# STM32.net
KiCad netlist of a schematic drawn in Altium Designer
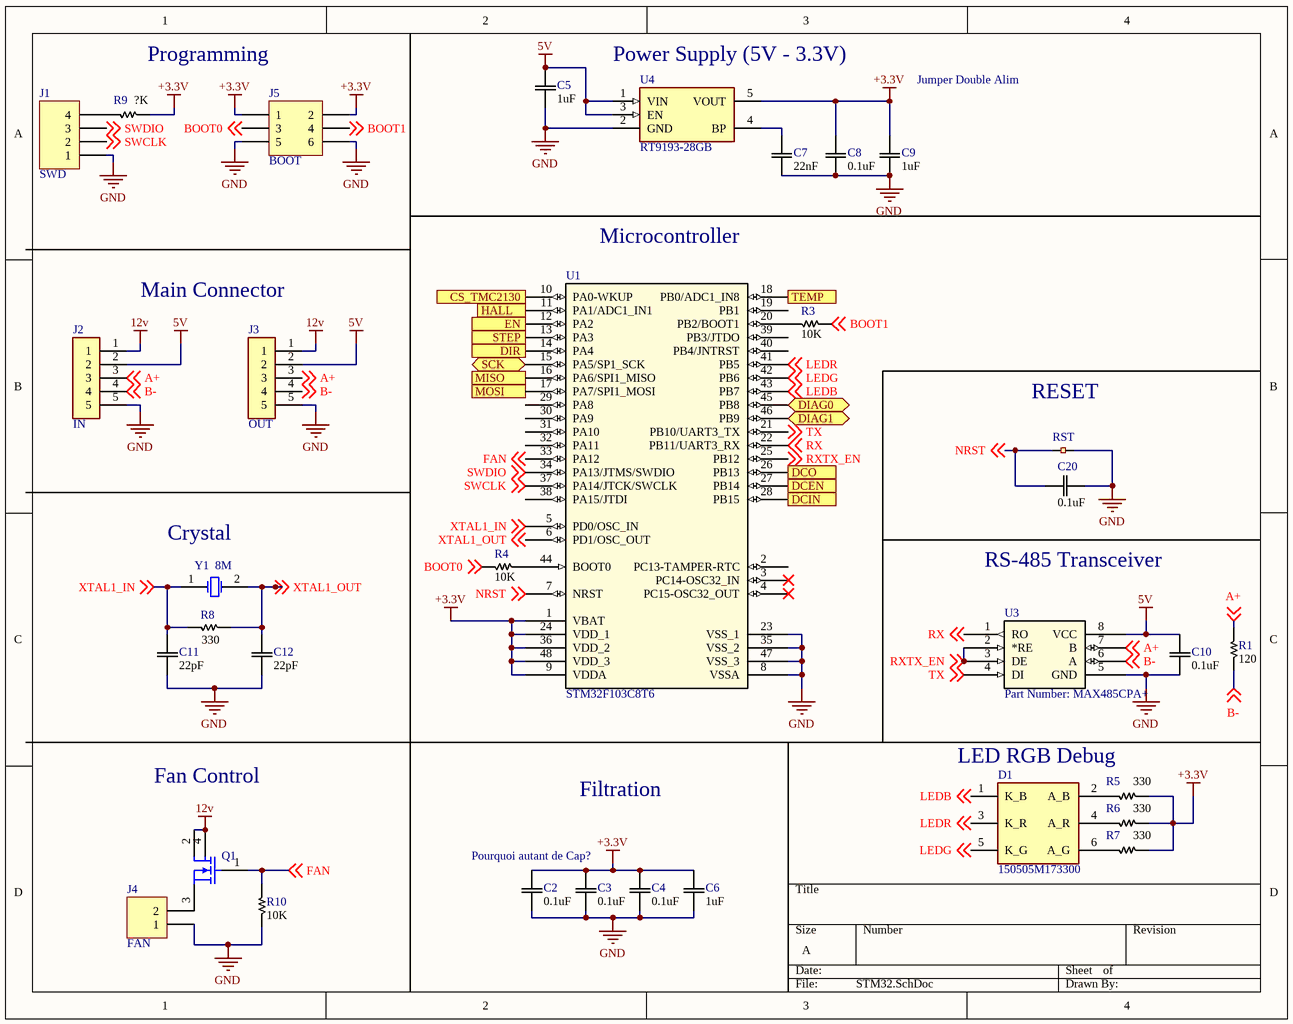
[diagram p0: STM32.SchDoc]

(export (version "E")
  (design (tool "Eeschema 10.0.6"))
  (components
    (comp (ref "C2")
      (value "0.1uF")
      (footprint "0603")
      (description "Capacitor SMD 1206")
      (fields
        (field (name "MANUFACTURER_PART_NUMBER") "12065A820JAT2A")
        (field (name "Comment") "Capacitor 1206")
        (field (name "COPYRIGHT") "Copyright (C) 2018 Accelerated Designs. All rights reserved")
      )
      (libsource (lib "Schematic_Emile") (part "Capacitor 1206"))
    )
    (comp (ref "C3")
      (value "0.1uF")
      (footprint "0603")
      (description "Capacitor SMD 1206")
      (fields
        (field (name "MANUFACTURER_PART_NUMBER") "12065A820JAT2A")
        (field (name "Comment") "Capacitor 1206")
        (field (name "COPYRIGHT") "Copyright (C) 2018 Accelerated Designs. All rights reserved")
      )
      (libsource (lib "Schematic_Emile") (part "Capacitor 1206"))
    )
    (comp (ref "C4")
      (value "0.1uF")
      (footprint "0603")
      (description "Capacitor SMD 1206")
      (fields
        (field (name "MANUFACTURER_PART_NUMBER") "12065A820JAT2A")
        (field (name "Comment") "Capacitor 1206")
        (field (name "COPYRIGHT") "Copyright (C) 2018 Accelerated Designs. All rights reserved")
      )
      (libsource (lib "Schematic_Emile") (part "Capacitor 1206"))
    )
    (comp (ref "C5")
      (value "1uF")
      (footprint "0603")
      (description "Capacitor SMD 1206")
      (fields
        (field (name "MANUFACTURER_PART_NUMBER") "12065A820JAT2A")
        (field (name "Comment") "Capacitor 1206")
        (field (name "COPYRIGHT") "Copyright (C) 2018 Accelerated Designs. All rights reserved")
      )
      (libsource (lib "Schematic_Emile") (part "Capacitor 1206"))
    )
    (comp (ref "C6")
      (value "1uF")
      (footprint "0603")
      (description "Capacitor SMD 1206")
      (fields
        (field (name "MANUFACTURER_PART_NUMBER") "12065A820JAT2A")
        (field (name "Comment") "Capacitor 1206")
        (field (name "COPYRIGHT") "Copyright (C) 2018 Accelerated Designs. All rights reserved")
      )
      (libsource (lib "Schematic_Emile") (part "Capacitor 1206"))
    )
    (comp (ref "C7")
      (value "22nF")
      (footprint "0603")
      (description "Capacitor SMD 1206")
      (fields
        (field (name "MANUFACTURER_PART_NUMBER") "12065A820JAT2A")
        (field (name "Comment") "Capacitor 1206")
        (field (name "COPYRIGHT") "Copyright (C) 2018 Accelerated Designs. All rights reserved")
      )
      (libsource (lib "Schematic_Emile") (part "Capacitor 1206"))
    )
    (comp (ref "C8")
      (value "0.1uF")
      (footprint "0603")
      (description "Capacitor SMD 1206")
      (fields
        (field (name "MANUFACTURER_PART_NUMBER") "12065A820JAT2A")
        (field (name "Comment") "Capacitor 1206")
        (field (name "COPYRIGHT") "Copyright (C) 2018 Accelerated Designs. All rights reserved")
      )
      (libsource (lib "Schematic_Emile") (part "Capacitor 1206"))
    )
    (comp (ref "C9")
      (value "1uF")
      (footprint "0603")
      (description "Capacitor SMD 1206")
      (fields
        (field (name "MANUFACTURER_PART_NUMBER") "12065A820JAT2A")
        (field (name "Comment") "Capacitor 1206")
        (field (name "COPYRIGHT") "Copyright (C) 2018 Accelerated Designs. All rights reserved")
      )
      (libsource (lib "Schematic_Emile") (part "Capacitor 1206"))
    )
    (comp (ref "C10")
      (value "0.1uF")
      (footprint "0603")
      (description "Capacitor SMD 1206")
      (fields
        (field (name "MANUFACTURER_PART_NUMBER") "12065A820JAT2A")
        (field (name "Comment") "Capacitor 1206")
        (field (name "COPYRIGHT") "Copyright (C) 2018 Accelerated Designs. All rights reserved")
      )
      (libsource (lib "Schematic_Emile") (part "Capacitor 1206"))
    )
    (comp (ref "C11")
      (value "22pF")
      (footprint "0603")
      (description "Capacitor SMD 1206")
      (fields
        (field (name "MANUFACTURER_PART_NUMBER") "12065A820JAT2A")
        (field (name "Comment") "Capacitor 1206")
        (field (name "COPYRIGHT") "Copyright (C) 2018 Accelerated Designs. All rights reserved")
      )
      (libsource (lib "Schematic_Emile") (part "Capacitor 1206"))
    )
    (comp (ref "C12")
      (value "22pF")
      (footprint "0603")
      (description "Capacitor SMD 1206")
      (fields
        (field (name "MANUFACTURER_PART_NUMBER") "12065A820JAT2A")
        (field (name "Comment") "Capacitor 1206")
        (field (name "COPYRIGHT") "Copyright (C) 2018 Accelerated Designs. All rights reserved")
      )
      (libsource (lib "Schematic_Emile") (part "Capacitor 1206"))
    )
    (comp (ref "C20")
      (value "0.1uF")
      (footprint "0603")
      (description "Capacitor SMD 1206")
      (fields
        (field (name "MANUFACTURER_PART_NUMBER") "12065A820JAT2A")
        (field (name "Comment") "Capacitor 1206")
        (field (name "COPYRIGHT") "Copyright (C) 2018 Accelerated Designs. All rights reserved")
      )
      (libsource (lib "Schematic_Emile") (part "Capacitor 1206"))
    )
    (comp (ref "D1")
      (value "150505M173300")
      (footprint "LED 5050")
      (description "LED")
      (fields
        (field (name "MOUSER PART NUMBER") "710-150505M173300")
        (field (name "RS PART NUMBER") "1766248P")
      )
      (libsource (lib "Schematic_Emile") (part "150505M173300"))
    )
    (comp (ref "J1")
      (value "SWD")
      (footprint "HDR1X4")
      (description "Header, 4-Pin")
      (fields (field (name "PUBLISHER") "Altium Limited"))
      (libsource (lib "Miscellaneous Connectors") (part "Header 4"))
    )
    (comp (ref "J2")
      (value "IN")
      (footprint "JST 5POS 2.5mm 90°")
      (description "Connector")
      (fields (field (name "MANUFACTURER_PART_NUMBER") "S5B-XH-A-1(LF)(SN)"))
      (libsource (lib "Schematic_Emile") (part "JST 5POS"))
    )
    (comp (ref "J3")
      (value "OUT")
      (footprint "JST 5POS 2.5mm 90°")
      (description "Connector")
      (fields (field (name "MANUFACTURER_PART_NUMBER") "S5B-XH-A-1(LF)(SN)"))
      (libsource (lib "Schematic_Emile") (part "JST 5POS"))
    )
    (comp (ref "J4")
      (value "FAN")
      (footprint "HDR1X2")
      (description "Header, 2-Pin")
      (fields (field (name "PUBLISHER") "Altium Limited"))
      (libsource (lib "Miscellaneous Connectors") (part "Header 2"))
    )
    (comp (ref "J5")
      (value "BOOT")
      (footprint "HDR2X3")
      (description "Header, 3-Pin, Dual row")
      (fields (field (name "PUBLISHER") "Altium Limited"))
      (libsource (lib "Miscellaneous Connectors") (part "Header 3X2"))
    )
    (comp (ref "Q1")
      (value "MOSFET N-CH")
      (footprint "SOT223_M")
      (description "55V 7A SOT223")
      (libsource (lib "Schematic_Emile") (part "MOSFET N-CH"))
    )
    (comp (ref "R1")
      (value "120")
      (footprint "0603")
      (description "Resistor 1206 SMD")
      (fields
        (field (name "MANUFACTURER_PART_NUMBER") "ERJ8CWFR024V")
        (field (name "Comment") "Resistor 1206")
        (field (name "COPYRIGHT") "Copyright (C) 2018 Accelerated Designs. All rights reserved")
      )
      (libsource (lib "Schematic_Emile") (part "Resistor 1206"))
    )
    (comp (ref "R3")
      (value "10K")
      (footprint "0603")
      (description "Resistor 1206 SMD")
      (fields
        (field (name "MANUFACTURER_PART_NUMBER") "ERJ8CWFR024V")
        (field (name "Comment") "Resistor 1206")
        (field (name "COPYRIGHT") "Copyright (C) 2018 Accelerated Designs. All rights reserved")
      )
      (libsource (lib "Schematic_Emile") (part "Resistor 1206"))
    )
    (comp (ref "R4")
      (value "10K")
      (footprint "0603")
      (description "Resistor 1206 SMD")
      (fields
        (field (name "MANUFACTURER_PART_NUMBER") "ERJ8CWFR024V")
        (field (name "Comment") "Resistor 1206")
        (field (name "COPYRIGHT") "Copyright (C) 2018 Accelerated Designs. All rights reserved")
      )
      (libsource (lib "Schematic_Emile") (part "Resistor 1206"))
    )
    (comp (ref "R5")
      (value "330")
      (footprint "0603")
      (description "Resistor 1206 SMD")
      (fields
        (field (name "MANUFACTURER_PART_NUMBER") "ERJ8CWFR024V")
        (field (name "Comment") "Resistor 1206")
        (field (name "COPYRIGHT") "Copyright (C) 2018 Accelerated Designs. All rights reserved")
      )
      (libsource (lib "Schematic_Emile") (part "Resistor 1206"))
    )
    (comp (ref "R6")
      (value "330")
      (footprint "0603")
      (description "Resistor 1206 SMD")
      (fields
        (field (name "MANUFACTURER_PART_NUMBER") "ERJ8CWFR024V")
        (field (name "Comment") "Resistor 1206")
        (field (name "COPYRIGHT") "Copyright (C) 2018 Accelerated Designs. All rights reserved")
      )
      (libsource (lib "Schematic_Emile") (part "Resistor 1206"))
    )
    (comp (ref "R7")
      (value "330")
      (footprint "0603")
      (description "Resistor 1206 SMD")
      (fields
        (field (name "MANUFACTURER_PART_NUMBER") "ERJ8CWFR024V")
        (field (name "Comment") "Resistor 1206")
        (field (name "COPYRIGHT") "Copyright (C) 2018 Accelerated Designs. All rights reserved")
      )
      (libsource (lib "Schematic_Emile") (part "Resistor 1206"))
    )
    (comp (ref "R8")
      (value "330")
      (footprint "0603")
      (description "Resistor 1206 SMD")
      (fields
        (field (name "MANUFACTURER_PART_NUMBER") "ERJ8CWFR024V")
        (field (name "Comment") "Resistor 1206")
        (field (name "COPYRIGHT") "Copyright (C) 2018 Accelerated Designs. All rights reserved")
      )
      (libsource (lib "Schematic_Emile") (part "Resistor 1206"))
    )
    (comp (ref "R9")
      (value "?K")
      (footprint "0603")
      (description "Resistor 1206 SMD")
      (fields
        (field (name "MANUFACTURER_PART_NUMBER") "ERJ8CWFR024V")
        (field (name "Comment") "Resistor 1206")
        (field (name "COPYRIGHT") "Copyright (C) 2018 Accelerated Designs. All rights reserved")
      )
      (libsource (lib "Schematic_Emile") (part "Resistor 1206"))
    )
    (comp (ref "R10")
      (value "10K")
      (footprint "0603")
      (description "Resistor 1206 SMD")
      (fields
        (field (name "MANUFACTURER_PART_NUMBER") "ERJ8CWFR024V")
        (field (name "Comment") "Resistor 1206")
        (field (name "COPYRIGHT") "Copyright (C) 2018 Accelerated Designs. All rights reserved")
      )
      (libsource (lib "Schematic_Emile") (part "Resistor 1206"))
    )
    (comp (ref "RST")
      (value "PAD")
      (footprint "PAD")
      (description "SMD Pad for contact")
      (libsource (lib "Schematic_Emile") (part "PAD"))
    )
    (comp (ref "U1")
      (value "STM32F103C8T6")
      (footprint "LQFP-48")
      (description "Integrated Circuit STM32")
      (fields (field (name "COPYRIGHT") "Copyright (C) 2018 Accelerated Designs. All rights reserved"))
      (libsource (lib "Schematic_Emile") (part "STM32F103C8T6"))
    )
    (comp (ref "U3")
      (value "Part Number: MAX485CPA+")
      (footprint "DIP 8 - 3D")
      (description "RS485 Communication")
      (fields
        (field (name "MANUFACTURER_PART_NUMBER") "MAX485CPA+")
        (field (name "COPYRIGHT") "Copyright (C) 2018 Accelerated Designs. All rights reserved")
      )
      (libsource (lib "Schematic_Emile") (part "MAX485CPA+"))
    )
    (comp (ref "U4")
      (value "RT9193-28GB")
      (footprint "SamacSys:SOT94P279X130-5N")
      (description "Voltage Regulator 3.3V")
      (libsource (lib "Schematic_Emile") (part "RT9193-28GB"))
    )
    (comp (ref "Y1")
      (value "8M")
      (footprint "ATS080B-E")
      (description "Crystal Oscillator")
      (fields (field (name "PUBLISHER") "Altium Limited"))
      (libsource (lib "Miscellaneous Devices") (part "XTAL"))
    )
  )
  (nets
    (net (code "1") (name "+3.3V") (class "Default")
      (node (ref "C2") (pin "2") (pinfunction "2_2") (pintype "passive"))
      (node (ref "C3") (pin "2") (pinfunction "2_2") (pintype "passive"))
      (node (ref "C4") (pin "2") (pinfunction "2_2") (pintype "passive"))
      (node (ref "C6") (pin "2") (pinfunction "2_2") (pintype "passive"))
      (node (ref "C8") (pin "2") (pinfunction "2_2") (pintype "passive"))
      (node (ref "C9") (pin "2") (pinfunction "2_2") (pintype "passive"))
      (node (ref "J5") (pin "1") (pinfunction "1_1") (pintype "passive"))
      (node (ref "J5") (pin "2") (pinfunction "2_2") (pintype "passive"))
      (node (ref "R5") (pin "2") (pinfunction "2_2") (pintype "passive"))
      (node (ref "R6") (pin "2") (pinfunction "2_2") (pintype "passive"))
      (node (ref "R7") (pin "2") (pinfunction "2_2") (pintype "passive"))
      (node (ref "R9") (pin "2") (pinfunction "2_2") (pintype "passive"))
      (node (ref "U1") (pin "1") (pinfunction "VBAT_1") (pintype "power_in"))
      (node (ref "U1") (pin "24") (pinfunction "VDD_1_24") (pintype "power_in"))
      (node (ref "U1") (pin "36") (pinfunction "VDD_2_36") (pintype "power_in"))
      (node (ref "U1") (pin "48") (pinfunction "VDD_3_48") (pintype "power_in"))
      (node (ref "U1") (pin "9") (pinfunction "VDDA_9") (pintype "power_in"))
      (node (ref "U4") (pin "5") (pinfunction "VOUT_5") (pintype "passive"))
    )
    (net (code "2") (name "/CS_TMC2130") (class "Default")
      (node (ref "U1") (pin "10") (pinfunction "PA0-WKUP_10") (pintype "bidirectional"))
    )
    (net (code "3") (name "/DCEN") (class "Default")
      (node (ref "U1") (pin "27") (pinfunction "PB14_27") (pintype "bidirectional"))
    )
    (net (code "4") (name "/DCIN") (class "Default")
      (node (ref "U1") (pin "28") (pinfunction "PB15_28") (pintype "bidirectional"))
    )
    (net (code "5") (name "/DCO") (class "Default")
      (node (ref "U1") (pin "26") (pinfunction "PB13_26") (pintype "bidirectional"))
    )
    (net (code "6") (name "/DIAG0") (class "Default")
      (node (ref "U1") (pin "45") (pinfunction "PB8_45") (pintype "bidirectional"))
    )
    (net (code "7") (name "/DIAG1") (class "Default")
      (node (ref "U1") (pin "46") (pinfunction "PB9_46") (pintype "bidirectional"))
    )
    (net (code "8") (name "/DIR") (class "Default")
      (node (ref "U1") (pin "14") (pinfunction "PA4_14") (pintype "bidirectional"))
    )
    (net (code "9") (name "/EN") (class "Default")
      (node (ref "U1") (pin "12") (pinfunction "PA2_12") (pintype "bidirectional"))
    )
    (net (code "10") (name "/HALL") (class "Default")
      (node (ref "U1") (pin "11") (pinfunction "PA1/ADC1_IN1_11") (pintype "bidirectional"))
    )
    (net (code "11") (name "/MISO") (class "Default")
      (node (ref "U1") (pin "16") (pinfunction "PA6/SPI1_MISO_16") (pintype "bidirectional"))
    )
    (net (code "12") (name "/MOSI") (class "Default")
      (node (ref "U1") (pin "17") (pinfunction "PA7/SPI1_MOSI_17") (pintype "bidirectional"))
    )
    (net (code "13") (name "/SCK") (class "Default")
      (node (ref "U1") (pin "15") (pinfunction "PA5/SP1_SCK_15") (pintype "bidirectional"))
    )
    (net (code "14") (name "/STEP") (class "Default")
      (node (ref "U1") (pin "13") (pinfunction "PA3_13") (pintype "bidirectional"))
    )
    (net (code "15") (name "/TEMP") (class "Default")
      (node (ref "U1") (pin "18") (pinfunction "PB0/ADC1_IN8_18") (pintype "bidirectional"))
    )
    (net (code "16") (name "5V") (class "Default")
      (node (ref "C10") (pin "2") (pinfunction "2_2") (pintype "passive"))
      (node (ref "C5") (pin "2") (pinfunction "2_2") (pintype "passive"))
      (node (ref "J2") (pin "2") (pinfunction "2_2") (pintype "passive"))
      (node (ref "J3") (pin "2") (pinfunction "2_2") (pintype "passive"))
      (node (ref "U3") (pin "8") (pinfunction "VCC_8") (pintype "power_in"))
      (node (ref "U4") (pin "1") (pinfunction "VIN_1") (pintype "input"))
      (node (ref "U4") (pin "3") (pinfunction "EN_3") (pintype "input"))
    )
    (net (code "17") (name "12v") (class "Default")
      (node (ref "J2") (pin "1") (pinfunction "1_1") (pintype "passive"))
      (node (ref "J3") (pin "1") (pinfunction "1_1") (pintype "passive"))
      (node (ref "Q1") (pin "2") (pinfunction "D_2") (pintype "passive"))
      (node (ref "Q1") (pin "4") (pinfunction "D_4") (pintype "passive"))
    )
    (net (code "18") (name "A+") (class "Default")
      (node (ref "J2") (pin "3") (pinfunction "3_3") (pintype "passive"))
      (node (ref "J3") (pin "3") (pinfunction "3_3") (pintype "passive"))
      (node (ref "R1") (pin "2") (pinfunction "2_2") (pintype "passive"))
      (node (ref "U3") (pin "7") (pinfunction "B_7") (pintype "bidirectional"))
    )
    (net (code "19") (name "B-") (class "Default")
      (node (ref "J2") (pin "4") (pinfunction "4_4") (pintype "passive"))
      (node (ref "J3") (pin "4") (pinfunction "4_4") (pintype "passive"))
      (node (ref "R1") (pin "1") (pinfunction "1_1") (pintype "passive"))
      (node (ref "U3") (pin "6") (pinfunction "A_6") (pintype "bidirectional"))
    )
    (net (code "20") (name "BOOT0") (class "Default")
      (node (ref "J5") (pin "3") (pinfunction "3_3") (pintype "passive"))
      (node (ref "R4") (pin "1") (pinfunction "1_1") (pintype "passive"))
    )
    (net (code "21") (name "BOOT1") (class "Default")
      (node (ref "J5") (pin "4") (pinfunction "4_4") (pintype "passive"))
      (node (ref "R3") (pin "2") (pinfunction "2_2") (pintype "passive"))
    )
    (net (code "22") (name "FAN") (class "Default")
      (node (ref "Q1") (pin "1") (pinfunction "G_1") (pintype "passive"))
      (node (ref "R10") (pin "2") (pinfunction "2_2") (pintype "passive"))
      (node (ref "U1") (pin "33") (pinfunction "PA12_33") (pintype "bidirectional"))
    )
    (net (code "23") (name "GND") (class "Default")
      (node (ref "C10") (pin "1") (pinfunction "1_1") (pintype "passive"))
      (node (ref "C11") (pin "1") (pinfunction "1_1") (pintype "passive"))
      (node (ref "C12") (pin "1") (pinfunction "1_1") (pintype "passive"))
      (node (ref "C2") (pin "1") (pinfunction "1_1") (pintype "passive"))
      (node (ref "C20") (pin "1") (pinfunction "1_1") (pintype "passive"))
      (node (ref "C3") (pin "1") (pinfunction "1_1") (pintype "passive"))
      (node (ref "C4") (pin "1") (pinfunction "1_1") (pintype "passive"))
      (node (ref "C5") (pin "1") (pinfunction "1_1") (pintype "passive"))
      (node (ref "C6") (pin "1") (pinfunction "1_1") (pintype "passive"))
      (node (ref "C7") (pin "1") (pinfunction "1_1") (pintype "passive"))
      (node (ref "C8") (pin "1") (pinfunction "1_1") (pintype "passive"))
      (node (ref "C9") (pin "1") (pinfunction "1_1") (pintype "passive"))
      (node (ref "J1") (pin "1") (pinfunction "1_1") (pintype "passive"))
      (node (ref "J2") (pin "5") (pinfunction "5_5") (pintype "passive"))
      (node (ref "J3") (pin "5") (pinfunction "5_5") (pintype "passive"))
      (node (ref "J4") (pin "1") (pinfunction "1_1") (pintype "passive"))
      (node (ref "J5") (pin "5") (pinfunction "5_5") (pintype "passive"))
      (node (ref "J5") (pin "6") (pinfunction "6_6") (pintype "passive"))
      (node (ref "R10") (pin "1") (pinfunction "1_1") (pintype "passive"))
      (node (ref "RST") (pin "1") (pinfunction "1_1") (pintype "passive"))
      (node (ref "U1") (pin "23") (pinfunction "VSS_1_23") (pintype "power_in"))
      (node (ref "U1") (pin "35") (pinfunction "VSS_2_35") (pintype "power_in"))
      (node (ref "U1") (pin "47") (pinfunction "VSS_3_47") (pintype "power_in"))
      (node (ref "U1") (pin "8") (pinfunction "VSSA_8") (pintype "power_in"))
      (node (ref "U3") (pin "5") (pinfunction "GND_5") (pintype "power_in"))
      (node (ref "U4") (pin "2") (pinfunction "GND_2") (pintype "power_in"))
    )
    (net (code "24") (name "LEDB") (class "Default")
      (node (ref "D1") (pin "1") (pinfunction "K_B_1") (pintype "passive"))
      (node (ref "U1") (pin "43") (pinfunction "PB7_43") (pintype "bidirectional"))
    )
    (net (code "25") (name "LEDG") (class "Default")
      (node (ref "D1") (pin "5") (pinfunction "K_G_5") (pintype "passive"))
      (node (ref "U1") (pin "42") (pinfunction "PB6_42") (pintype "bidirectional"))
    )
    (net (code "26") (name "LEDR") (class "Default")
      (node (ref "D1") (pin "3") (pinfunction "K_R_3") (pintype "passive"))
      (node (ref "U1") (pin "41") (pinfunction "PB5_41") (pintype "bidirectional"))
    )
    (net (code "27") (name "NRST") (class "Default")
      (node (ref "C20") (pin "2") (pinfunction "2_2") (pintype "passive"))
      (node (ref "RST") (pin "2") (pinfunction "2_2") (pintype "passive"))
      (node (ref "U1") (pin "7") (pinfunction "NRST_7") (pintype "bidirectional"))
    )
    (net (code "28") (name "Net-(D1-A_B)") (class "Default")
      (node (ref "D1") (pin "2") (pinfunction "A_B_2") (pintype "passive"))
      (node (ref "R5") (pin "1") (pinfunction "1_1") (pintype "passive"))
    )
    (net (code "29") (name "Net-(D1-A_G)") (class "Default")
      (node (ref "D1") (pin "6") (pinfunction "A_G_6") (pintype "passive"))
      (node (ref "R7") (pin "1") (pinfunction "1_1") (pintype "passive"))
    )
    (net (code "30") (name "Net-(D1-A_R)") (class "Default")
      (node (ref "D1") (pin "4") (pinfunction "A_R_4") (pintype "passive"))
      (node (ref "R6") (pin "1") (pinfunction "1_1") (pintype "passive"))
    )
    (net (code "31") (name "Net-(J1-Pad4)") (class "Default")
      (node (ref "J1") (pin "4") (pinfunction "4_4") (pintype "passive"))
      (node (ref "R9") (pin "1") (pinfunction "1_1") (pintype "passive"))
    )
    (net (code "32") (name "Net-(Q1-S)") (class "Default")
      (node (ref "J4") (pin "2") (pinfunction "2_2") (pintype "passive"))
      (node (ref "Q1") (pin "3") (pinfunction "S_3") (pintype "passive"))
    )
    (net (code "33") (name "Net-(U1-BOOT0)") (class "Default")
      (node (ref "R4") (pin "2") (pinfunction "2_2") (pintype "passive"))
      (node (ref "U1") (pin "44") (pinfunction "BOOT0_44") (pintype "input"))
    )
    (net (code "34") (name "Net-(U1-PB2{slash}BOOT1)") (class "Default")
      (node (ref "R3") (pin "1") (pinfunction "1_1") (pintype "passive"))
      (node (ref "U1") (pin "20") (pinfunction "PB2/BOOT1_20") (pintype "bidirectional"))
    )
    (net (code "35") (name "Net-(U4-BP)") (class "Default")
      (node (ref "C7") (pin "2") (pinfunction "2_2") (pintype "passive"))
      (node (ref "U4") (pin "4") (pinfunction "BP_4") (pintype "passive"))
    )
    (net (code "36") (name "RX") (class "Default")
      (node (ref "U1") (pin "22") (pinfunction "PB11/UART3_RX_22") (pintype "bidirectional"))
      (node (ref "U3") (pin "1") (pinfunction "RO_1") (pintype "output"))
    )
    (net (code "37") (name "RXTX_EN") (class "Default")
      (node (ref "U1") (pin "25") (pinfunction "PB12_25") (pintype "bidirectional"))
      (node (ref "U3") (pin "2") (pinfunction "*RE_2") (pintype "input"))
      (node (ref "U3") (pin "3") (pinfunction "DE_3") (pintype "input"))
    )
    (net (code "38") (name "SWCLK") (class "Default")
      (node (ref "J1") (pin "2") (pinfunction "2_2") (pintype "passive"))
      (node (ref "U1") (pin "37") (pinfunction "PA14/JTCK/SWCLK_37") (pintype "bidirectional"))
    )
    (net (code "39") (name "SWDIO") (class "Default")
      (node (ref "J1") (pin "3") (pinfunction "3_3") (pintype "passive"))
      (node (ref "U1") (pin "34") (pinfunction "PA13/JTMS/SWDIO_34") (pintype "bidirectional"))
    )
    (net (code "40") (name "TX") (class "Default")
      (node (ref "U1") (pin "21") (pinfunction "PB10/UART3_TX_21") (pintype "bidirectional"))
      (node (ref "U3") (pin "4") (pinfunction "DI_4") (pintype "input"))
    )
    (net (code "41") (name "XTAL1_IN") (class "Default")
      (node (ref "C11") (pin "2") (pinfunction "2_2") (pintype "passive"))
      (node (ref "R8") (pin "1") (pinfunction "1_1") (pintype "passive"))
      (node (ref "U1") (pin "5") (pinfunction "PD0/OSC_IN_5") (pintype "bidirectional"))
      (node (ref "Y1") (pin "1") (pinfunction "OSC1_1") (pintype "passive"))
    )
    (net (code "42") (name "XTAL1_OUT") (class "Default")
      (node (ref "C12") (pin "2") (pinfunction "2_2") (pintype "passive"))
      (node (ref "R8") (pin "2") (pinfunction "2_2") (pintype "passive"))
      (node (ref "U1") (pin "6") (pinfunction "PD1/OSC_OUT_6") (pintype "bidirectional"))
      (node (ref "Y1") (pin "2") (pinfunction "OSC2_2") (pintype "passive"))
    )
    (net (code "43") (name "unconnected-(U1-PA8-Pad29)") (class "Default")
      (node (ref "U1") (pin "29") (pinfunction "PA8_29") (pintype "bidirectional"))
    )
    (net (code "44") (name "unconnected-(U1-PA9-Pad30)") (class "Default")
      (node (ref "U1") (pin "30") (pinfunction "PA9_30") (pintype "bidirectional"))
    )
    (net (code "45") (name "unconnected-(U1-PA10-Pad31)") (class "Default")
      (node (ref "U1") (pin "31") (pinfunction "PA10_31") (pintype "bidirectional"))
    )
    (net (code "46") (name "unconnected-(U1-PA11-Pad32)") (class "Default")
      (node (ref "U1") (pin "32") (pinfunction "PA11_32") (pintype "bidirectional"))
    )
    (net (code "47") (name "unconnected-(U1-PA15{slash}JTDI-Pad38)") (class "Default")
      (node (ref "U1") (pin "38") (pinfunction "PA15/JTDI_38") (pintype "bidirectional"))
    )
    (net (code "48") (name "unconnected-(U1-PB1-Pad19)") (class "Default")
      (node (ref "U1") (pin "19") (pinfunction "PB1_19") (pintype "bidirectional"))
    )
    (net (code "49") (name "unconnected-(U1-PB3{slash}JTDO-Pad39)") (class "Default")
      (node (ref "U1") (pin "39") (pinfunction "PB3/JTDO_39") (pintype "bidirectional"))
    )
    (net (code "50") (name "unconnected-(U1-PB4{slash}JNTRST-Pad40)") (class "Default")
      (node (ref "U1") (pin "40") (pinfunction "PB4/JNTRST_40") (pintype "bidirectional"))
    )
    (net (code "51") (name "unconnected-(U1-PC13-TAMPER-RTC-Pad2)") (class "Default")
      (node (ref "U1") (pin "2") (pinfunction "PC13-TAMPER-RTC_2") (pintype "bidirectional"))
    )
    (net (code "52") (name "unconnected-(U1-PC14-OSC32_IN-Pad3)") (class "Default")
      (node (ref "U1") (pin "3") (pinfunction "PC14-OSC32_IN_3") (pintype "bidirectional+no_connect"))
    )
    (net (code "53") (name "unconnected-(U1-PC15-OSC32_OUT-Pad4)") (class "Default")
      (node (ref "U1") (pin "4") (pinfunction "PC15-OSC32_OUT_4") (pintype "bidirectional+no_connect"))
    )
  )
)
